# Lynx_Shield.net
KiCad netlist of a schematic drawn in EAGLE
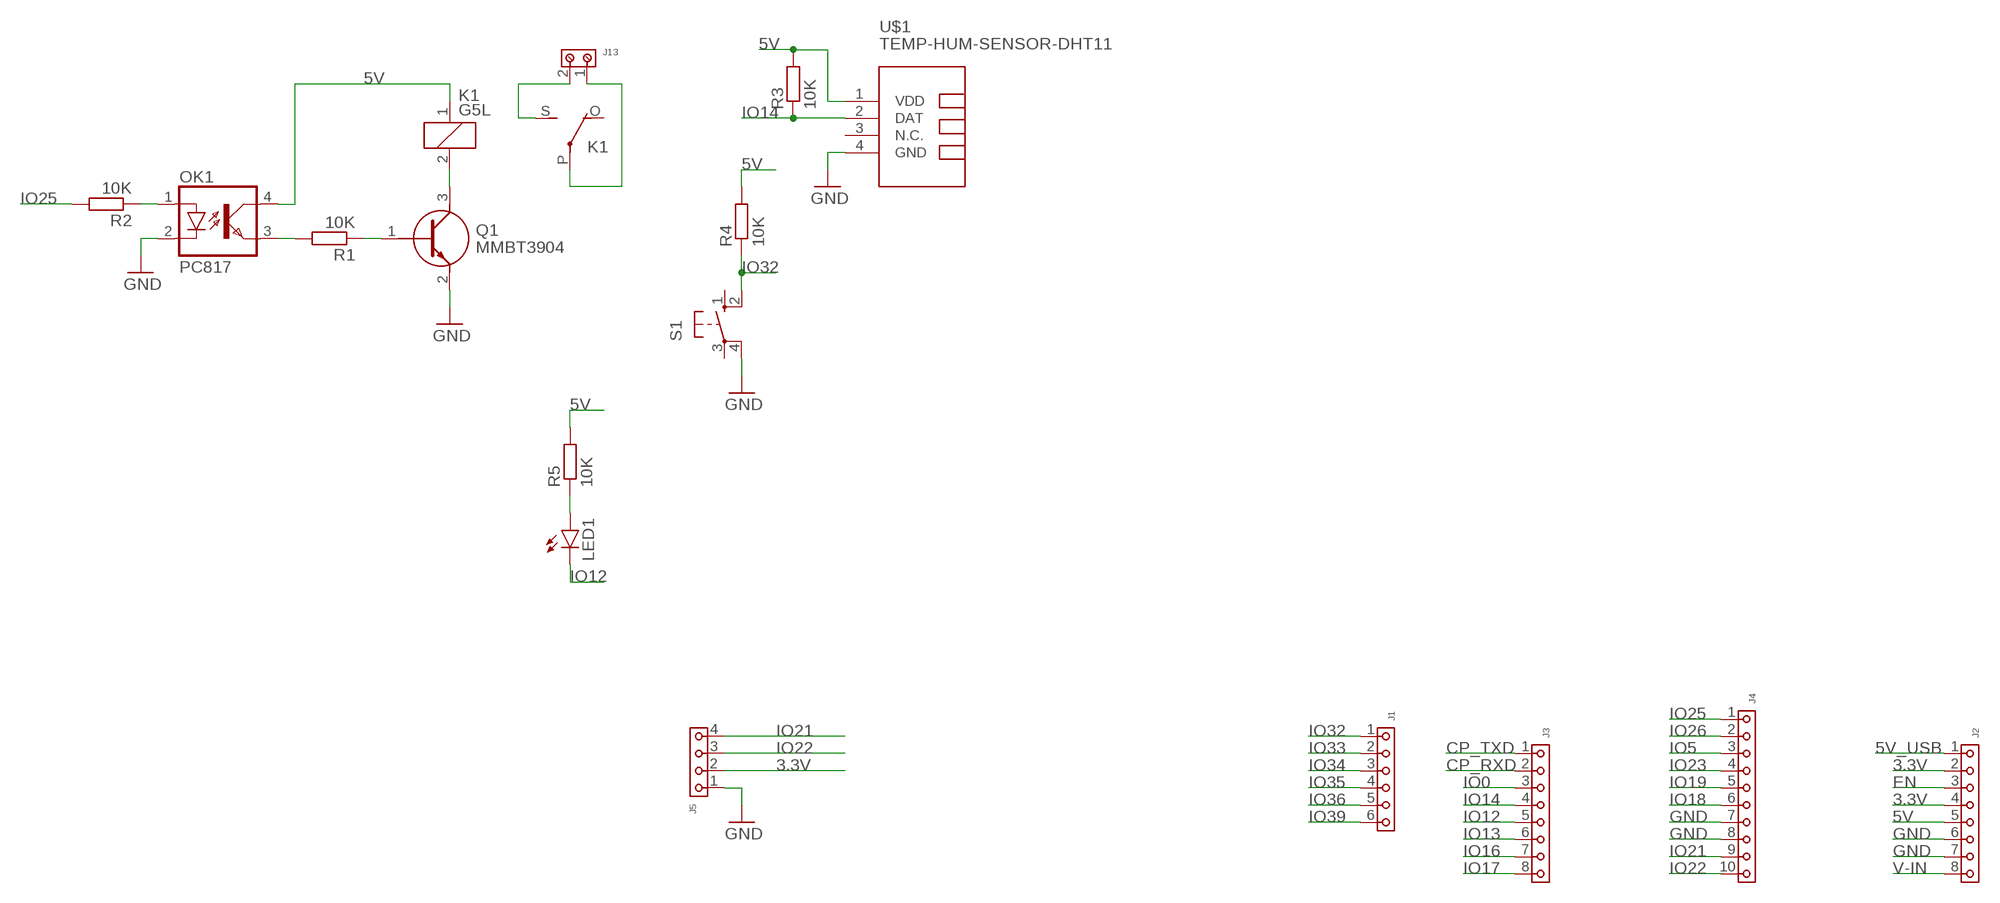
[diagram p0: schematic, sheet 1]

(export (version "E")
  (design (tool "Eeschema 10.0.6"))
  (components
    (comp (ref "J1")
      (value "6130XX11821_61300611821")
      (footprint "eagle-import:61300611821")
      (libsource (lib "eagle-import") (part "6130XX11821_61300611821"))
    )
    (comp (ref "J2")
      (value "6130XX11821_61300811821")
      (footprint "eagle-import:61300811821")
      (libsource (lib "eagle-import") (part "6130XX11821_61300811821"))
    )
    (comp (ref "J3")
      (value "6130XX11821_61300811821")
      (footprint "eagle-import:61300811821")
      (libsource (lib "eagle-import") (part "6130XX11821_61300811821"))
    )
    (comp (ref "J4")
      (value "6130XX11821_61301011821")
      (footprint "eagle-import:61301011821")
      (libsource (lib "eagle-import") (part "6130XX11821_61301011821"))
    )
    (comp (ref "J5")
      (value "6130XX11821_61300411821")
      (footprint "eagle-import:61300411821")
      (libsource (lib "eagle-import") (part "6130XX11821_61300411821"))
    )
    (comp (ref "J13")
      (value "691134710002")
      (footprint "eagle-import:691134710002")
      (libsource (lib "eagle-import") (part "691134710002"))
    )
    (comp (ref "K1")
      (value "G5L")
      (footprint "eagle-import:G5LE")
      (libsource (lib "eagle-import") (part "G5L"))
    )
    (comp (ref "LED1")
      (value "LED5MM")
      (footprint "eagle-import:LED5MM")
      (libsource (lib "eagle-import") (part "LED5MM"))
    )
    (comp (ref "OK1")
      (value "PC817")
      (footprint "eagle-import:DIL04")
      (fields (field (name "MPN") "PC817X4J000F"))
      (libsource (lib "eagle-import") (part "PC817"))
    )
    (comp (ref "Q1")
      (value "MMBT3904")
      (footprint "eagle-import:SOT95P240X120-3N")
      (fields (field (name "MOUSER_PART_NUMBER") "512-MMBT3904"))
      (libsource (lib "eagle-import") (part "MMBT3904"))
    )
    (comp (ref "R1")
      (value "10K")
      (footprint "eagle-import:R0603")
      (libsource (lib "eagle-import") (part "R-EU_R0603"))
    )
    (comp (ref "R2")
      (value "10K")
      (footprint "eagle-import:R0603")
      (libsource (lib "eagle-import") (part "R-EU_R0603"))
    )
    (comp (ref "R3")
      (value "10K")
      (footprint "eagle-import:R0603")
      (libsource (lib "eagle-import") (part "R-EU_R0603"))
    )
    (comp (ref "R4")
      (value "10K")
      (footprint "eagle-import:R0603")
      (libsource (lib "eagle-import") (part "R-EU_R0603"))
    )
    (comp (ref "R5")
      (value "10K")
      (footprint "eagle-import:R0603")
      (libsource (lib "eagle-import") (part "R-EU_R0603"))
    )
    (comp (ref "S1")
      (value "10-XX")
      (footprint "eagle-import:B3F-10XX")
      (fields (field (name "MPN") "B3F-1000"))
      (libsource (lib "eagle-import") (part "10-XX"))
    )
    (comp (ref "U$1")
      (value "TEMP-HUM-SENSOR-DHT11")
      (footprint "eagle-import:TEMP-HUM-SENSOR-DHT11")
      (libsource (lib "eagle-import") (part "TEMP-HUM-SENSOR-DHT11"))
    )
  )
  (nets
    (net (code "1") (name "/3.3V") (class "Default")
      (node (ref "J2") (pin "2") (pinfunction "2_2") (pintype "passive"))
      (node (ref "J2") (pin "4") (pinfunction "4_4") (pintype "passive"))
      (node (ref "J5") (pin "2") (pinfunction "2_2") (pintype "passive"))
    )
    (net (code "2") (name "/5V") (class "Default")
      (node (ref "J2") (pin "5") (pinfunction "5_5") (pintype "passive"))
      (node (ref "K1") (pin "1") (pinfunction "1_1") (pintype "passive"))
      (node (ref "OK1") (pin "4") (pinfunction "COL_4") (pintype "passive"))
      (node (ref "R3") (pin "2") (pinfunction "2_2") (pintype "passive"))
      (node (ref "R4") (pin "2") (pinfunction "2_2") (pintype "passive"))
      (node (ref "R5") (pin "2") (pinfunction "2_2") (pintype "passive"))
      (node (ref "U$1") (pin "1") (pinfunction "VDD_1") (pintype "power_in"))
    )
    (net (code "3") (name "/5V_USB") (class "Default")
      (node (ref "J2") (pin "1") (pinfunction "1_1") (pintype "passive"))
    )
    (net (code "4") (name "/CP_RXD") (class "Default")
      (node (ref "J3") (pin "2") (pinfunction "2_2") (pintype "passive"))
    )
    (net (code "5") (name "/CP_TXD") (class "Default")
      (node (ref "J3") (pin "1") (pinfunction "1_1") (pintype "passive"))
    )
    (net (code "6") (name "/EN") (class "Default")
      (node (ref "J2") (pin "3") (pinfunction "3_3") (pintype "passive"))
    )
    (net (code "7") (name "/IO0") (class "Default")
      (node (ref "J3") (pin "3") (pinfunction "3_3") (pintype "passive"))
    )
    (net (code "8") (name "/IO5") (class "Default")
      (node (ref "J4") (pin "3") (pinfunction "3_3") (pintype "passive"))
    )
    (net (code "9") (name "/IO12") (class "Default")
      (node (ref "J3") (pin "5") (pinfunction "5_5") (pintype "passive"))
      (node (ref "LED1") (pin "K") (pinfunction "C_K") (pintype "passive"))
    )
    (net (code "10") (name "/IO13") (class "Default")
      (node (ref "J3") (pin "6") (pinfunction "6_6") (pintype "passive"))
    )
    (net (code "11") (name "/IO14") (class "Default")
      (node (ref "J3") (pin "4") (pinfunction "4_4") (pintype "passive"))
      (node (ref "R3") (pin "1") (pinfunction "1_1") (pintype "passive"))
      (node (ref "U$1") (pin "2") (pinfunction "DAT_2") (pintype "bidirectional"))
    )
    (net (code "12") (name "/IO16") (class "Default")
      (node (ref "J3") (pin "7") (pinfunction "7_7") (pintype "passive"))
    )
    (net (code "13") (name "/IO17") (class "Default")
      (node (ref "J3") (pin "8") (pinfunction "8_8") (pintype "passive"))
    )
    (net (code "14") (name "/IO18") (class "Default")
      (node (ref "J4") (pin "6") (pinfunction "6_6") (pintype "passive"))
    )
    (net (code "15") (name "/IO19") (class "Default")
      (node (ref "J4") (pin "5") (pinfunction "5_5") (pintype "passive"))
    )
    (net (code "16") (name "/IO21") (class "Default")
      (node (ref "J4") (pin "9") (pinfunction "9_9") (pintype "passive"))
      (node (ref "J5") (pin "4") (pinfunction "4_4") (pintype "passive"))
    )
    (net (code "17") (name "/IO22") (class "Default")
      (node (ref "J4") (pin "10") (pinfunction "10_10") (pintype "passive"))
      (node (ref "J5") (pin "3") (pinfunction "3_3") (pintype "passive"))
    )
    (net (code "18") (name "/IO23") (class "Default")
      (node (ref "J4") (pin "4") (pinfunction "4_4") (pintype "passive"))
    )
    (net (code "19") (name "/IO25") (class "Default")
      (node (ref "J4") (pin "1") (pinfunction "1_1") (pintype "passive"))
      (node (ref "R2") (pin "2") (pinfunction "2_2") (pintype "passive"))
    )
    (net (code "20") (name "/IO26") (class "Default")
      (node (ref "J4") (pin "2") (pinfunction "2_2") (pintype "passive"))
    )
    (net (code "21") (name "/IO32") (class "Default")
      (node (ref "J1") (pin "1") (pinfunction "1_1") (pintype "passive"))
      (node (ref "R4") (pin "1") (pinfunction "1_1") (pintype "passive"))
      (node (ref "S1") (pin "2") (pinfunction "S1_2") (pintype "passive"))
    )
    (net (code "22") (name "/IO33") (class "Default")
      (node (ref "J1") (pin "2") (pinfunction "2_2") (pintype "passive"))
    )
    (net (code "23") (name "/IO34") (class "Default")
      (node (ref "J1") (pin "3") (pinfunction "3_3") (pintype "passive"))
    )
    (net (code "24") (name "/IO35") (class "Default")
      (node (ref "J1") (pin "4") (pinfunction "4_4") (pintype "passive"))
    )
    (net (code "25") (name "/IO36") (class "Default")
      (node (ref "J1") (pin "5") (pinfunction "5_5") (pintype "passive"))
    )
    (net (code "26") (name "/IO39") (class "Default")
      (node (ref "J1") (pin "6") (pinfunction "6_6") (pintype "passive"))
    )
    (net (code "27") (name "/V-IN") (class "Default")
      (node (ref "J2") (pin "8") (pinfunction "8_8") (pintype "passive"))
    )
    (net (code "28") (name "GND") (class "Default")
      (node (ref "J2") (pin "6") (pinfunction "6_6") (pintype "passive"))
      (node (ref "J2") (pin "7") (pinfunction "7_7") (pintype "passive"))
      (node (ref "J4") (pin "7") (pinfunction "7_7") (pintype "passive"))
      (node (ref "J4") (pin "8") (pinfunction "8_8") (pintype "passive"))
      (node (ref "J5") (pin "1") (pinfunction "1_1") (pintype "passive"))
      (node (ref "OK1") (pin "2") (pinfunction "C_2") (pintype "passive"))
      (node (ref "Q1") (pin "2") (pinfunction "E_2") (pintype "bidirectional"))
      (node (ref "S1") (pin "4") (pinfunction "P1_4") (pintype "passive"))
      (node (ref "U$1") (pin "4") (pinfunction "GND_4") (pintype "power_in"))
    )
    (net (code "29") (name "Net-(J13-Pad1)") (class "Default")
      (node (ref "J13") (pin "1") (pinfunction "1_1") (pintype "passive"))
      (node (ref "K1") (pin "P") (pinfunction "P_P") (pintype "passive"))
    )
    (net (code "30") (name "Net-(J13-Pad2)") (class "Default")
      (node (ref "J13") (pin "2") (pinfunction "2_2") (pintype "passive"))
      (node (ref "K1") (pin "S") (pinfunction "S_S") (pintype "passive"))
    )
    (net (code "31") (name "Net-(LED1-PadA)") (class "Default")
      (node (ref "LED1") (pin "A") (pinfunction "A_A") (pintype "passive"))
      (node (ref "R5") (pin "1") (pinfunction "1_1") (pintype "passive"))
    )
    (net (code "32") (name "Net-(OK1-A)") (class "Default")
      (node (ref "OK1") (pin "1") (pinfunction "A_1") (pintype "passive"))
      (node (ref "R2") (pin "1") (pinfunction "1_1") (pintype "passive"))
    )
    (net (code "33") (name "Net-(OK1-EMIT)") (class "Default")
      (node (ref "OK1") (pin "3") (pinfunction "EMIT_3") (pintype "passive"))
      (node (ref "R1") (pin "2") (pinfunction "2_2") (pintype "passive"))
    )
    (net (code "34") (name "Net-(Q1-B)") (class "Default")
      (node (ref "Q1") (pin "1") (pinfunction "B_1") (pintype "bidirectional"))
      (node (ref "R1") (pin "1") (pinfunction "1_1") (pintype "passive"))
    )
    (net (code "35") (name "Net-(Q1-C)") (class "Default")
      (node (ref "K1") (pin "2") (pinfunction "2_2") (pintype "passive"))
      (node (ref "Q1") (pin "3") (pinfunction "C_3") (pintype "bidirectional"))
    )
    (net (code "36") (name "unconnected-(K1-PadO)") (class "Default")
      (node (ref "K1") (pin "O") (pinfunction "O_O") (pintype "passive"))
    )
    (net (code "37") (name "unconnected-(S1-P-Pad3)") (class "Default")
      (node (ref "S1") (pin "3") (pinfunction "P_3") (pintype "passive"))
    )
    (net (code "38") (name "unconnected-(S1-S-Pad1)") (class "Default")
      (node (ref "S1") (pin "1") (pinfunction "S_1") (pintype "passive"))
    )
    (net (code "39") (name "unconnected-(U$1-N.C.-Pad3)") (class "Default")
      (node (ref "U$1") (pin "3") (pinfunction "N.C._3") (pintype "passive"))
    )
  )
)
